# LED_Driver.net
KiCad netlist of a schematic drawn in Altium Designer
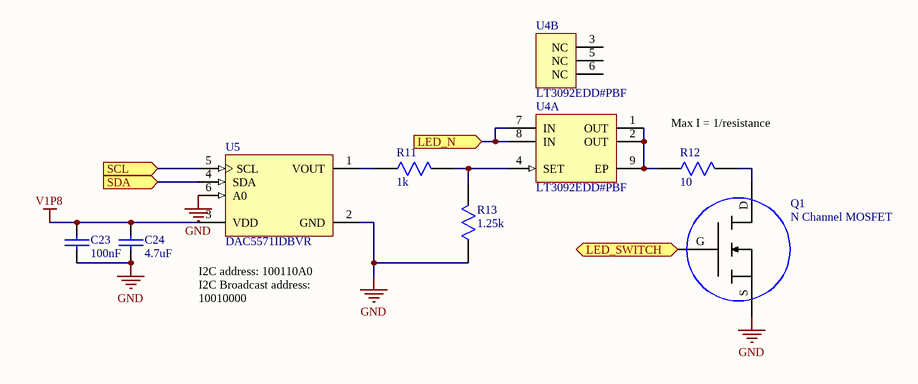
[diagram p0: LED_Driver.SchDoc]

(export (version "E")
  (design (tool "Eeschema 10.0.6"))
  (components
    (comp (ref "C23")
      (value "100nF")
      (footprint "SMD CAP 0402")
      (libsource (lib "DA_Component_Library") (part "Capacitor"))
    )
    (comp (ref "C24")
      (value "4.7uF")
      (footprint "SMD CAP 0402")
      (libsource (lib "DA_Component_Library") (part "Capacitor"))
    )
    (comp (ref "Q1")
      (value "N Channel MOSFET")
      (footprint "NTK3134N")
      (libsource (lib "DA_Component_Library") (part "N Channel MOSFET"))
    )
    (comp (ref "R11")
      (value "1k")
      (footprint "SMD RES 0402")
      (libsource (lib "DA_Component_Library") (part "Resistor"))
    )
    (comp (ref "R12")
      (value "10")
      (footprint "SMD RES 0402")
      (libsource (lib "DA_Component_Library") (part "Resistor"))
    )
    (comp (ref "R13")
      (value "1.25k")
      (footprint "SMD RES 0402")
      (libsource (lib "DA_Component_Library") (part "Resistor"))
    )
    (comp (ref "U4")
      (value "LT3092EDD#PBF")
      (footprint "LT-DD-8_V")
      (fields (field (name "MANUFACTURER") "Linear Technology"))
      (libsource (lib "Linear Technology Power Management Current Sources") (part "LT3092EDD#PBF"))
    )
    (comp (ref "U5")
      (value "DAC5571IDBVR")
      (footprint "TI-DBV6_M")
      (fields (field (name "MANUFACTURER") "Texas Instruments"))
      (libsource (lib "TI Data Converters Digital to Analog Converter") (part "DAC5571IDBVR"))
    )
  )
  (nets
    (net (code "1") (name "/LED_N") (class "Default")
      (node (ref "U4") (pin "7") (pinfunction "IN_7") (pintype "power_in"))
      (node (ref "U4") (pin "8") (pinfunction "IN_8") (pintype "power_in"))
    )
    (net (code "2") (name "/LED_SWITCH") (class "Default") (node (ref "Q1") (pin "G") (pintype "passive")))
    (net (code "3") (name "/SCL") (class "Default")
      (node (ref "U5") (pin "5") (pinfunction "SCL_5") (pintype "input"))
    )
    (net (code "4") (name "/SDA") (class "Default")
      (node (ref "U5") (pin "4") (pinfunction "SDA_4") (pintype "input"))
    )
    (net (code "5") (name "GND") (class "Default")
      (node (ref "C23") (pin "1") (pinfunction "1_1") (pintype "passive"))
      (node (ref "C24") (pin "1") (pinfunction "1_1") (pintype "passive"))
      (node (ref "Q1") (pin "S") (pintype "passive"))
      (node (ref "R13") (pin "0") (pinfunction "0_0") (pintype "passive"))
      (node (ref "U5") (pin "2") (pinfunction "GND_2") (pintype "power_in"))
      (node (ref "U5") (pin "6") (pinfunction "A0_6") (pintype "input"))
    )
    (net (code "6") (name "Net-(Q1-PadD)") (class "Default")
      (node (ref "Q1") (pin "D") (pintype "passive"))
      (node (ref "R12") (pin "1") (pinfunction "1_1") (pintype "passive"))
    )
    (net (code "7") (name "Net-(U4A-EP)") (class "Default")
      (node (ref "R12") (pin "0") (pinfunction "0_0") (pintype "passive"))
      (node (ref "U4") (pin "1") (pinfunction "OUT_1") (pintype "power_in"))
      (node (ref "U4") (pin "2") (pinfunction "OUT_2") (pintype "power_in"))
      (node (ref "U4") (pin "9") (pinfunction "EP_9") (pintype "power_in"))
    )
    (net (code "8") (name "Net-(U4A-SET)") (class "Default")
      (node (ref "R11") (pin "1") (pinfunction "1_1") (pintype "passive"))
      (node (ref "R13") (pin "1") (pinfunction "1_1") (pintype "passive"))
      (node (ref "U4") (pin "4") (pinfunction "SET_4") (pintype "input"))
    )
    (net (code "9") (name "Net-(U5-VOUT)") (class "Default")
      (node (ref "R11") (pin "0") (pinfunction "0_0") (pintype "passive"))
      (node (ref "U5") (pin "1") (pinfunction "VOUT_1") (pintype "tri_state"))
    )
    (net (code "10") (name "V1P8") (class "Default")
      (node (ref "C23") (pin "0") (pinfunction "0_0") (pintype "passive"))
      (node (ref "C24") (pin "0") (pinfunction "0_0") (pintype "passive"))
      (node (ref "U5") (pin "3") (pinfunction "VDD_3") (pintype "power_in"))
    )
    (net (code "11") (name "unconnected-(U4B-NC-Pad3)") (class "Default")
      (node (ref "U4") (pin "3") (pinfunction "NC_3") (pintype "passive"))
    )
    (net (code "12") (name "unconnected-(U4B-NC-Pad5)") (class "Default")
      (node (ref "U4") (pin "5") (pinfunction "NC_5") (pintype "passive"))
    )
    (net (code "13") (name "unconnected-(U4B-NC-Pad6)") (class "Default")
      (node (ref "U4") (pin "6") (pinfunction "NC_6") (pintype "passive"))
    )
  )
)
